# Power_Sheet.net
KiCad netlist of a schematic drawn in Altium Designer
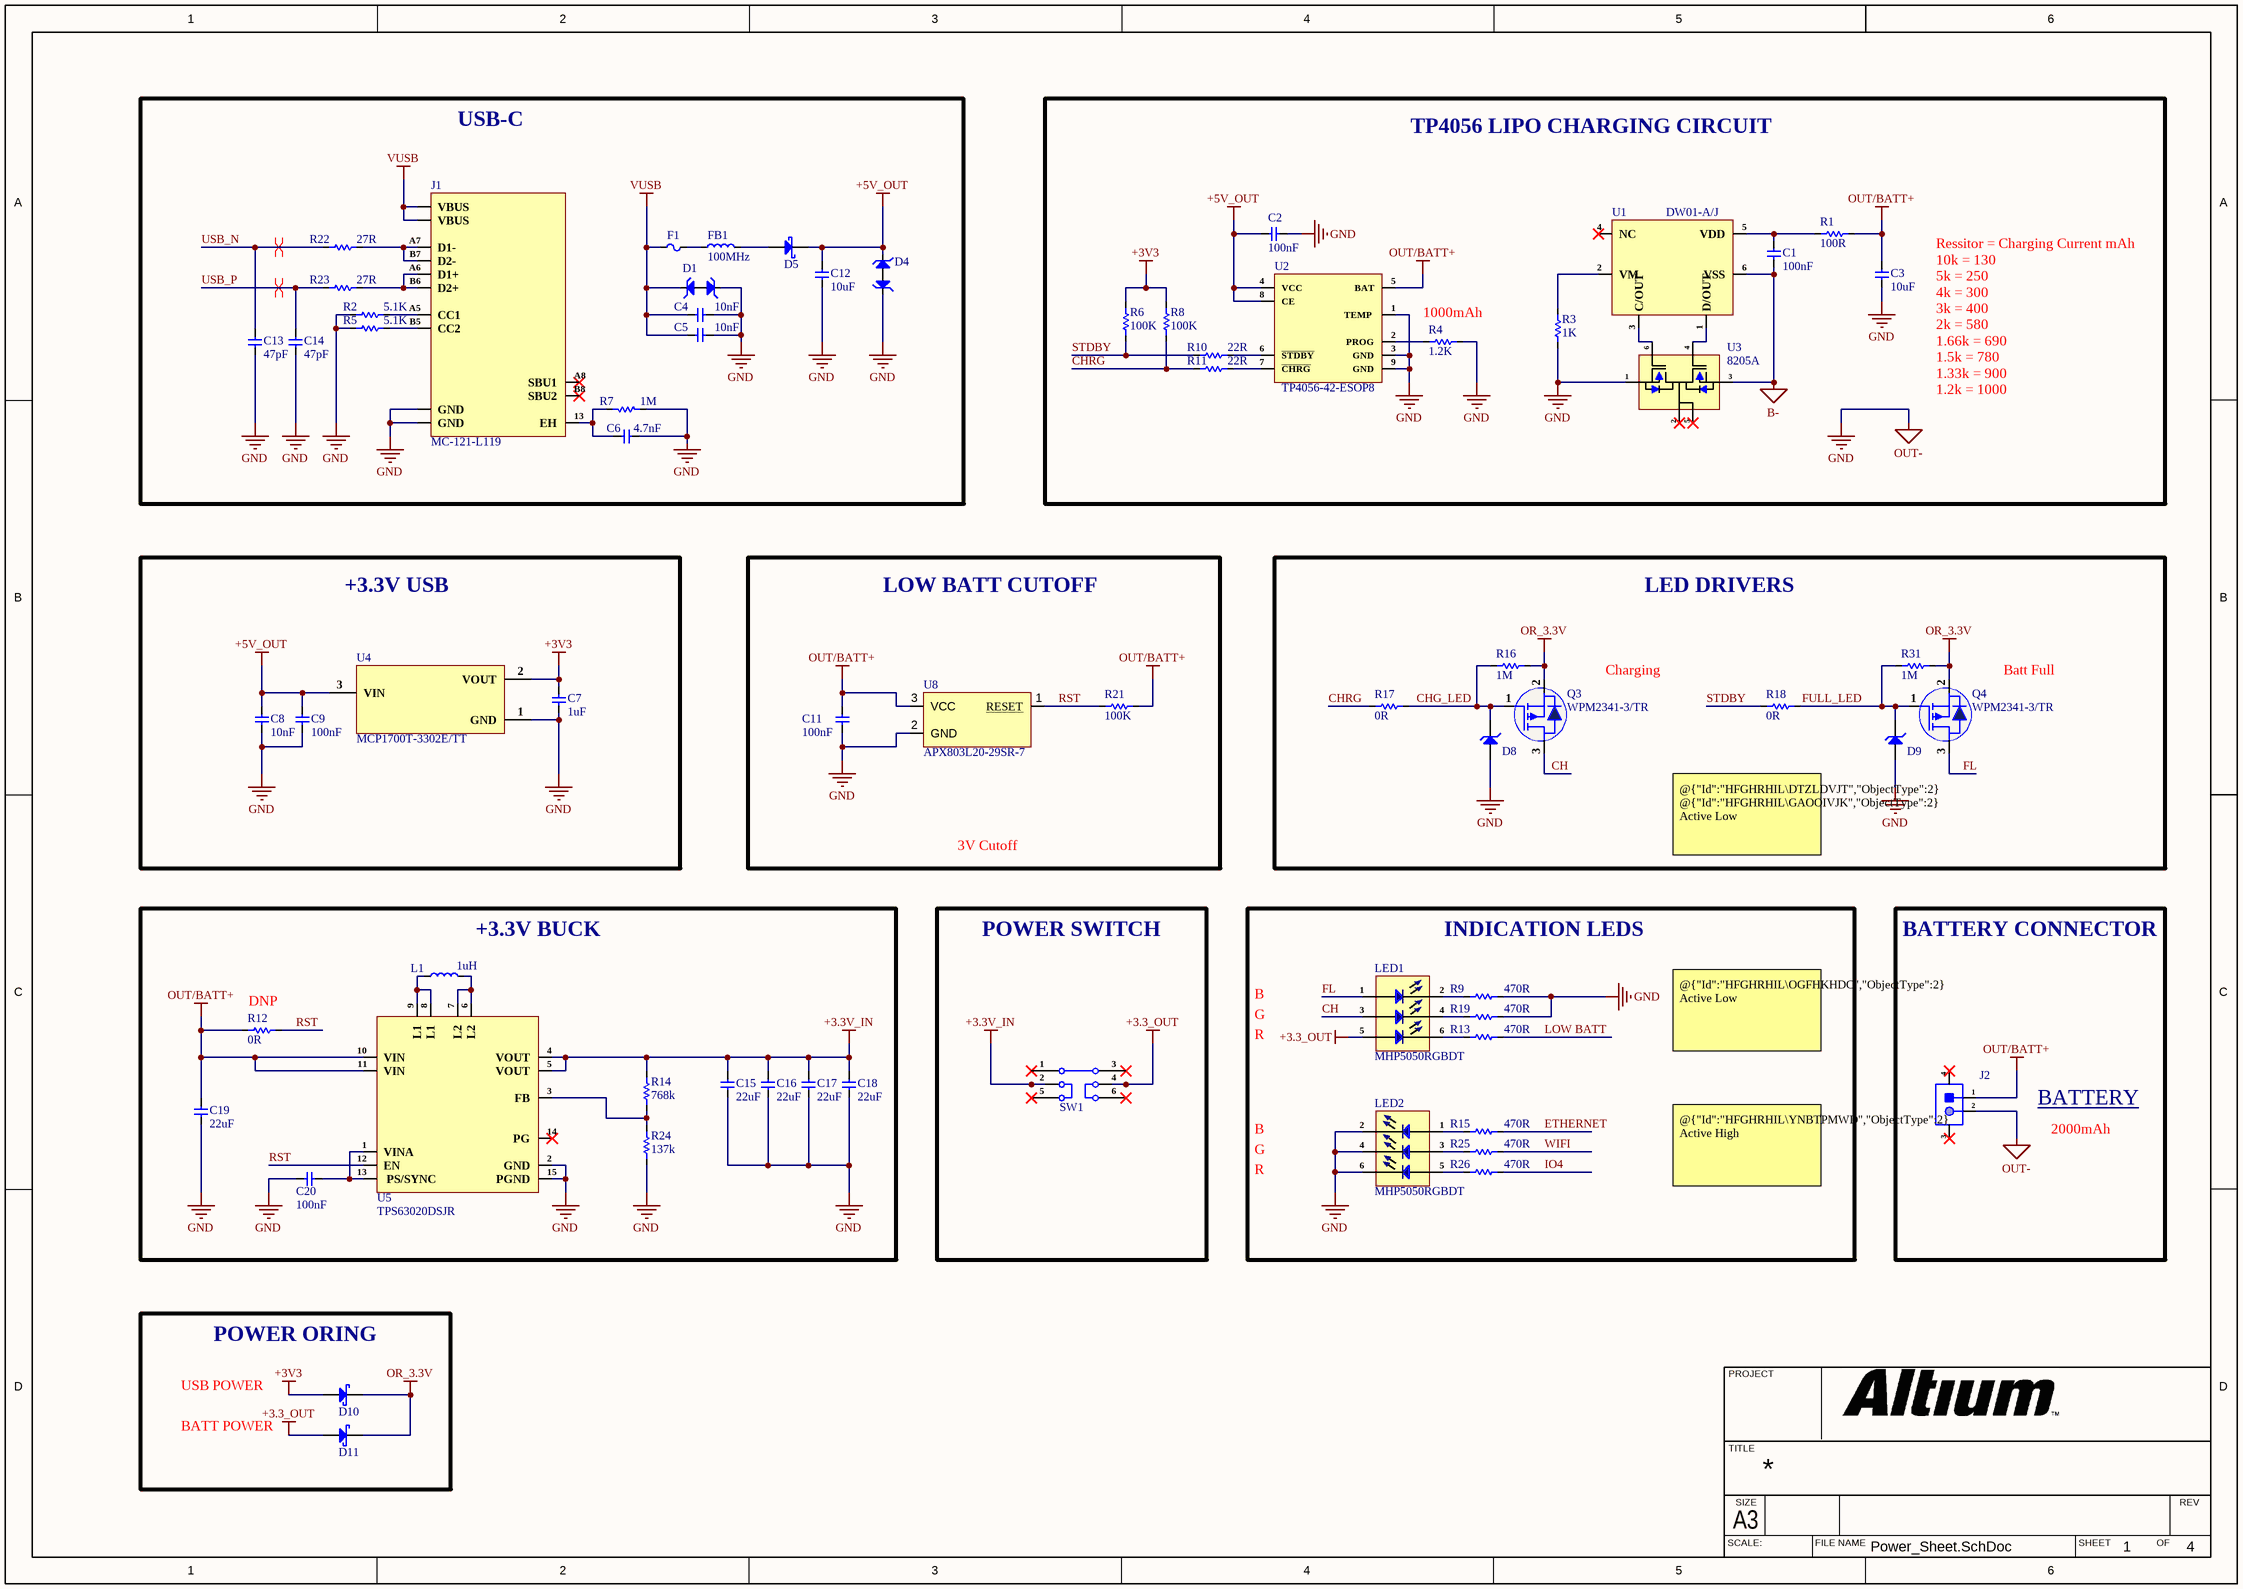
[diagram p0: Power_Sheet.SchDoc]

(export (version "E")
  (design (tool "Eeschema 10.0.6"))
  (components
    (comp (ref "C1")
      (value "100nF")
      (footprint "cap-0402")
      (description "CAP CER 0.1UF 50V X7R 0402")
      (fields
        (field (name "MANUFACTURER") "TDK")
        (field (name "MANUFACTURER PART NUMBER") "C1005X7R1H104KT000F")
      )
      (libsource (lib "eSpark Libraries") (part "C1005X7R1H104KT000F"))
    )
    (comp (ref "C2")
      (value "100nF")
      (footprint "cap-0402")
      (description "CAP CER 0.1UF 50V X7R 0402")
      (fields
        (field (name "MANUFACTURER") "TDK")
        (field (name "MANUFACTURER PART NUMBER") "C1005X7R1H104KT000F")
      )
      (libsource (lib "eSpark Libraries") (part "C1005X7R1H104KT000F"))
    )
    (comp (ref "C3")
      (value "10uF")
      (footprint "Cap-0402")
      (description "CAP CER 10UF 10V X5R 0402")
      (fields
        (field (name "MANUFACTURER") "Samsung")
        (field (name "MANUFACTURER PART NUMBER") "CL05A106MP5NUNC")
      )
      (libsource (lib "eSpark Libraries") (part "CL05A106MP5NUNC"))
    )
    (comp (ref "C4")
      (value "10nF")
      (footprint "Cap-0402")
      (description "CAP CER 10000PF 25V X7R 0402")
      (fields
        (field (name "MANUFACTURER") "Yageo")
        (field (name "MANUFACTURER PART NUMBER") "CC0402KRX7R8BB103")
      )
      (libsource (lib "eSpark Libraries") (part "CC0402KRX7R8BB103"))
    )
    (comp (ref "C5")
      (value "10nF")
      (footprint "Cap-0402")
      (description "CAP CER 10000PF 25V X7R 0402")
      (fields
        (field (name "MANUFACTURER") "Yageo")
        (field (name "MANUFACTURER PART NUMBER") "CC0402KRX7R8BB103")
      )
      (libsource (lib "eSpark Libraries") (part "CC0402KRX7R8BB103"))
    )
    (comp (ref "C6")
      (value "4.7nF")
      (footprint "Cap-0402")
      (description "CAP CER 4700PF 50V X7R 0402")
      (fields
        (field (name "MANUFACTURER") "Yageo")
        (field (name "MANUFACTURER PART NUMBER") "CC0402KRX7R9BB472")
      )
      (libsource (lib "eSpark Libraries") (part "CC0402KRX7R9BB472"))
    )
    (comp (ref "C7")
      (value "1uF")
      (footprint "Cap-0402")
      (description "CAP CER 1UF 10V X5R 0402")
      (fields
        (field (name "MANUFACTURER") "Yageo")
        (field (name "MANUFACTURER PART NUMBER") "CC0402KRX5R6BB105")
      )
      (libsource (lib "eSpark Libraries") (part "CC0402KRX5R6BB105"))
    )
    (comp (ref "C8")
      (value "10nF")
      (footprint "Cap-0402")
      (description "CAP CER 10000PF 25V X7R 0402")
      (fields
        (field (name "MANUFACTURER") "Yageo")
        (field (name "MANUFACTURER PART NUMBER") "CC0402KRX7R8BB103")
      )
      (libsource (lib "eSpark Libraries") (part "CC0402KRX7R8BB103"))
    )
    (comp (ref "C9")
      (value "100nF")
      (footprint "cap-0402")
      (description "CAP CER 0.1UF 50V X7R 0402")
      (fields
        (field (name "MANUFACTURER") "TDK")
        (field (name "MANUFACTURER PART NUMBER") "C1005X7R1H104KT000F")
      )
      (libsource (lib "eSpark Libraries") (part "C1005X7R1H104KT000F"))
    )
    (comp (ref "C11")
      (value "100nF")
      (footprint "cap-0402")
      (description "CAP CER 0.1UF 50V X7R 0402")
      (fields
        (field (name "MANUFACTURER") "TDK")
        (field (name "MANUFACTURER PART NUMBER") "C1005X7R1H104KT000F")
      )
      (libsource (lib "eSpark Libraries") (part "C1005X7R1H104KT000F"))
    )
    (comp (ref "C12")
      (value "10uF")
      (footprint "Cap-0603")
      (description "CAP CER 10UF 25V X5R 0603")
      (fields
        (field (name "MANUFACTURER") "Samsung")
        (field (name "MANUFACTURER PART NUMBER") "CL10A106MA8NRNC")
      )
      (libsource (lib "eSpark Libraries") (part "CL10A106MA8NRNC"))
    )
    (comp (ref "C13")
      (value "47pF")
      (footprint "Cap-0402")
      (description "CAP CER 47PF 50V C0G/NP0 0402")
      (fields
        (field (name "MANUFACTURER") "Murata")
        (field (name "MANUFACTURER PART NUMBER") "GCM1555C1H470FA16D")
      )
      (libsource (lib "eSpark Libraries") (part "GCM1555C1H470FA16D"))
    )
    (comp (ref "C14")
      (value "47pF")
      (footprint "Cap-0402")
      (description "CAP CER 47PF 50V C0G/NP0 0402")
      (fields
        (field (name "MANUFACTURER") "Murata")
        (field (name "MANUFACTURER PART NUMBER") "GCM1555C1H470FA16D")
      )
      (libsource (lib "eSpark Libraries") (part "GCM1555C1H470FA16D"))
    )
    (comp (ref "C15")
      (value "22uF")
      (footprint "Cap-0805")
      (description "CAP CER 22UF 35V X5R 0805")
      (fields
        (field (name "MANUFACTURER") "TDK Corporation")
        (field (name "MANUFACTURER PART NUMBER") "C2012X5R1V226MT000E")
      )
      (libsource (lib "eSpark Libraries") (part "C2012X5R1V226MT000E"))
    )
    (comp (ref "C16")
      (value "22uF")
      (footprint "Cap-0805")
      (description "CAP CER 22UF 35V X5R 0805")
      (fields
        (field (name "MANUFACTURER") "TDK Corporation")
        (field (name "MANUFACTURER PART NUMBER") "C2012X5R1V226MT000E")
      )
      (libsource (lib "eSpark Libraries") (part "C2012X5R1V226MT000E"))
    )
    (comp (ref "C17")
      (value "22uF")
      (footprint "Cap-0805")
      (description "CAP CER 22UF 35V X5R 0805")
      (fields
        (field (name "MANUFACTURER") "TDK Corporation")
        (field (name "MANUFACTURER PART NUMBER") "C2012X5R1V226MT000E")
      )
      (libsource (lib "eSpark Libraries") (part "C2012X5R1V226MT000E"))
    )
    (comp (ref "C18")
      (value "22uF")
      (footprint "Cap-0805")
      (description "CAP CER 22UF 35V X5R 0805")
      (fields
        (field (name "MANUFACTURER") "TDK Corporation")
        (field (name "MANUFACTURER PART NUMBER") "C2012X5R1V226MT000E")
      )
      (libsource (lib "eSpark Libraries") (part "C2012X5R1V226MT000E"))
    )
    (comp (ref "C19")
      (value "22uF")
      (footprint "Cap-0805")
      (description "CAP CER 22UF 35V X5R 0805")
      (fields
        (field (name "MANUFACTURER") "TDK Corporation")
        (field (name "MANUFACTURER PART NUMBER") "C2012X5R1V226MT000E")
      )
      (libsource (lib "eSpark Libraries") (part "C2012X5R1V226MT000E"))
    )
    (comp (ref "C20")
      (value "100nF")
      (footprint "cap-0402")
      (description "CAP CER 0.1UF 50V X7R 0402")
      (fields
        (field (name "MANUFACTURER") "TDK")
        (field (name "MANUFACTURER PART NUMBER") "C1005X7R1H104KT000F")
      )
      (libsource (lib "eSpark Libraries") (part "C1005X7R1H104KT000F"))
    )
    (comp (ref "D1")
      (value "PESD5V0H1BSFYL")
      (footprint "DSN0603-2")
      (description "TVS DIODE 5VWM 6.3VC DSN0603-2")
      (fields (field (name "MANUFACTURER") "Nexperia") (field (name "LCSC PART NUMBER") "C477989"))
      (libsource (lib "eSpark Libraries") (part "PESD5V0H1BSFYL"))
    )
    (comp (ref "D4")
      (value "PESD5V0H1BSFYL")
      (footprint "DSN0603-2")
      (description "TVS DIODE 5VWM 6.3VC DSN0603-2")
      (fields (field (name "MANUFACTURER") "Nexperia") (field (name "LCSC PART NUMBER") "C477989"))
      (libsource (lib "eSpark Libraries") (part "PESD5V0H1BSFYL"))
    )
    (comp (ref "D5")
      (value "PMEG3010ER,115")
      (footprint "SOD-123W")
      (description "DIODE SCHOTTKY 30V 1A SOD123W")
      (fields (field (name "MANUFACTURER") "Nexperia") (field (name "LCSC PART NUMBER") "C456106"))
      (libsource (lib "eSpark Libraries") (part "PMEG3010ER,115"))
    )
    (comp (ref "D8")
      (value "MM3Z3V3")
      (footprint "SOD-323")
      (description "±5% Single 3.1V~3.5V 300mW 3.3V SOD-323 Zener Diodes ROHS")
      (fields (field (name "MANUFACTURER") "JSMSEMI") (field (name "LCSC PART NUMBER") "C123917"))
      (libsource (lib "eSpark Libraries") (part "MM3Z3V3"))
    )
    (comp (ref "D9")
      (value "MM3Z3V3")
      (footprint "SOD-323")
      (description "±5% Single 3.1V~3.5V 300mW 3.3V SOD-323 Zener Diodes ROHS")
      (fields (field (name "MANUFACTURER") "JSMSEMI") (field (name "LCSC PART NUMBER") "C123917"))
      (libsource (lib "eSpark Libraries") (part "MM3Z3V3"))
    )
    (comp (ref "D10")
      (value "RB521S-30")
      (footprint "SOD-523")
      (description "30V 500mV@200mA 200mA SOD-523 Schottky Barrier Diodes (SBD) ROHS")
      (fields
        (field (name "MANUFACTURER") "Jiangsu Changjing Electronics")
        (field (name "LCSC PART NUMBER") "C8523")
      )
      (libsource (lib "eSpark Libraries") (part "RB521S-30"))
    )
    (comp (ref "D11")
      (value "RB521S-30")
      (footprint "SOD-523")
      (description "30V 500mV@200mA 200mA SOD-523 Schottky Barrier Diodes (SBD) ROHS")
      (fields
        (field (name "MANUFACTURER") "Jiangsu Changjing Electronics")
        (field (name "LCSC PART NUMBER") "C8523")
      )
      (libsource (lib "eSpark Libraries") (part "RB521S-30"))
    )
    (comp (ref "F1")
      (value "BSMD0805L-200")
      (footprint "Fuse-0805")
      (description "6V 2A 50A 1W -40℃~+85℃ 4A 4mΩ 5s 45mΩ 0805 Resettable Fuses ROHS")
      (fields (field (name "MANUFACTURER") "BHFUSE") (field (name "LCSC PART NUMBER") "C2757931"))
      (libsource (lib "eSpark Libraries") (part "BSMD0805L-200"))
    )
    (comp (ref "FB1")
      (value "100MHz")
      (footprint "IND-1206")
      (description "FERRITE BEAD 120 OHM 1206 1LN")
      (fields
        (field (name "MANUFACTURER") "Murata")
        (field (name "MANUFACTURER PART NUMBER") "BLM31PG121SN1L")
      )
      (libsource (lib "eSpark Libraries") (part "BLM31PG121SN1L"))
    )
    (comp (ref "J1")
      (value "MC-121-L119")
      (footprint "MC-121-L119")
      (description "5A USB 3.1 1 Surface Mount 16P Female -40℃~+85℃ Type-C SMD USB Connectors ROHS")
      (fields (field (name "MANUFACTURER") "Hanbo Electronic") (field (name "LCSC PART NUMBER") "C6332278"))
      (libsource (lib "eSpark Libraries") (part "MC-121-L119"))
    )
    (comp (ref "J2")
      (value "S2B-PH-SM4-TB(LF)(SN)")
      (footprint "S2B-PH-SM4-TB(LF)(SN)")
      (fields (field (name "MANUFACTURER") "JST") (field (name "LCSC PART NUMBER") "C295747"))
      (libsource (lib "eSpark Libraries") (part "S2B-PH-SM4-TB(LF)(SN)"))
    )
    (comp (ref "L1")
      (value "1uH")
      (footprint "IND-1008 (2520 Metric)")
      (description "FIXED IND 1UH 3.2A 0.042OHM SMD")
      (fields (field (name "LCSC PART NUMBER") "C882955") (field (name "MANUFACTURER") "Murata"))
      (libsource (lib "eSpark Libraries") (part "DFE252012P-1R0M=P2"))
    )
    (comp (ref "LED1")
      (value "MHP5050RGBDT")
      (footprint "MHP5050RGBDT")
      (description "20mA White Diffused -40℃~+85℃ RGB SMD5050 Light Emitting Diodes (LED) ROHS")
      (fields (field (name "MANUFACTURER") "MEIHUA") (field (name "LCSC PART NUMBER") "C409780"))
      (libsource (lib "") (part "MHP5050RGBDT_1"))
    )
    (comp (ref "LED2")
      (value "MHP5050RGBDT")
      (footprint "MHP5050RGBDT")
      (description "20mA White Diffused -40℃~+85℃ RGB SMD5050 Light Emitting Diodes (LED) ROHS")
      (fields (field (name "MANUFACTURER") "MEIHUA") (field (name "LCSC PART NUMBER") "C409780"))
      (libsource (lib "eSpark Libraries") (part "MHP5050RGBDT"))
    )
    (comp (ref "Q3")
      (value "WPM2341-3/TR")
      (footprint "Sot-23")
      (description "20V 3.5A 750mW 61mΩ@4.5V,3.3A 1V@250uA 1PCSPChannel SOT-23 MOSFETs ROHS")
      (fields (field (name "MANUFACTURER") "WILLSEMI") (field (name "LCSC PART NUMBER") "C167138"))
      (libsource (lib "eSpark Libraries") (part "WPM2341-3/TR"))
    )
    (comp (ref "Q4")
      (value "WPM2341-3/TR")
      (footprint "Sot-23")
      (description "20V 3.5A 750mW 61mΩ@4.5V,3.3A 1V@250uA 1PCSPChannel SOT-23 MOSFETs ROHS")
      (fields (field (name "MANUFACTURER") "WILLSEMI") (field (name "LCSC PART NUMBER") "C167138"))
      (libsource (lib "eSpark Libraries") (part "WPM2341-3/TR"))
    )
    (comp (ref "R1")
      (value "100R")
      (footprint "RES-0805")
      (description "RES SMD 100 OHM 1% 1/8W 0805")
      (fields
        (field (name "MANUFACTURER") "Yageo")
        (field (name "MANUFACTURER PART NUMBER") "AC0805FR-07100RL")
      )
      (libsource (lib "eSpark Libraries") (part "AC0805FR-07100RL"))
    )
    (comp (ref "R2")
      (value "5.1K")
      (footprint "Res-0402")
      (description "RES 5.1K OHM 1% 1/16W 0402")
      (fields
        (field (name "MANUFACTURER") "Yageo")
        (field (name "MANUFACTURER PART NUMBER") "RC0402FR-075K1L")
      )
      (libsource (lib "eSpark Libraries") (part "RC0402FR-075K1L"))
    )
    (comp (ref "R3")
      (value "1K")
      (footprint "Res-0402")
      (description "RES SMD 1K OHM 1% 1/5W 0402")
      (fields
        (field (name "MANUFACTURER") "Vishay Dale")
        (field (name "MANUFACTURER PART NUMBER") "CRCW04021K00FKEDHP")
      )
      (libsource (lib "eSpark Libraries") (part "CRCW04021K00FKEDHP"))
    )
    (comp (ref "R4")
      (value "1.2K")
      (footprint "Res-0402")
      (description "RES 1.2K OHM 1% 1/16W 0402")
      (fields
        (field (name "MANUFACTURER") "Yageo")
        (field (name "MANUFACTURER PART NUMBER") "RC0402FR-071K2L")
      )
      (libsource (lib "eSpark Libraries") (part "RC0402FR-071K2L"))
    )
    (comp (ref "R5")
      (value "5.1K")
      (footprint "Res-0402")
      (description "RES 5.1K OHM 1% 1/16W 0402")
      (fields
        (field (name "MANUFACTURER") "Yageo")
        (field (name "MANUFACTURER PART NUMBER") "RC0402FR-075K1L")
      )
      (libsource (lib "eSpark Libraries") (part "RC0402FR-075K1L"))
    )
    (comp (ref "R6")
      (value "100K")
      (footprint "Res-0402")
      (description "RES 100K OHM 1% 1/16W 0402")
      (fields
        (field (name "MANUFACTURER") "Yageo")
        (field (name "MANUFACTURER PART NUMBER") "RC0402FR-07100KL")
      )
      (libsource (lib "eSpark Libraries") (part "RC0402FR-07100KL"))
    )
    (comp (ref "R7")
      (value "1M")
      (footprint "Res-0402")
      (description "RES SMD 1M OHM 5% 1/16W 0402")
      (fields
        (field (name "MANUFACTURER") "Yageo")
        (field (name "MANUFACTURER PART NUMBER") "AF0402JR-071ML")
      )
      (libsource (lib "eSpark Libraries") (part "AF0402JR-071ML"))
    )
    (comp (ref "R8")
      (value "100K")
      (footprint "Res-0402")
      (description "RES 100K OHM 1% 1/16W 0402")
      (fields
        (field (name "MANUFACTURER") "Yageo")
        (field (name "MANUFACTURER PART NUMBER") "RC0402FR-07100KL")
      )
      (libsource (lib "eSpark Libraries") (part "RC0402FR-07100KL"))
    )
    (comp (ref "R9")
      (value "470R")
      (footprint "Res-0402")
      (description "RES 470 OHM 1% 1/16W 0402")
      (fields
        (field (name "MANUFACTURER") "Yageo")
        (field (name "MANUFACTURER PART NUMBER") "RC0402FR-07470RL")
      )
      (libsource (lib "eSpark Libraries") (part "RC0402FR-07470RL"))
    )
    (comp (ref "R10")
      (value "22R")
      (footprint "Res-0402")
      (description "RES 22 OHM 1% 1/16W 0402")
      (fields
        (field (name "MANUFACTURER") "Yageo")
        (field (name "MANUFACTURER PART NUMBER") "RC0402FR-0722RL")
      )
      (libsource (lib "eSpark Libraries") (part "RC0402FR-0722RL"))
    )
    (comp (ref "R11")
      (value "22R")
      (footprint "Res-0402")
      (description "RES 22 OHM 1% 1/16W 0402")
      (fields
        (field (name "MANUFACTURER") "Yageo")
        (field (name "MANUFACTURER PART NUMBER") "RC0402FR-0722RL")
      )
      (libsource (lib "eSpark Libraries") (part "RC0402FR-0722RL"))
    )
    (comp (ref "R12")
      (value "0R")
      (footprint "Res-0402")
      (description "RES 0 OHM JUMPER 1/16W 0402")
      (fields
        (field (name "MANUFACTURER") "Yageo")
        (field (name "MANUFACTURER PART NUMBER") "RC0402FR-070RL")
      )
      (libsource (lib "eSpark Libraries") (part "RC0402FR-070RL"))
    )
    (comp (ref "R13")
      (value "470R")
      (footprint "Res-0402")
      (description "RES 470 OHM 1% 1/16W 0402")
      (fields
        (field (name "MANUFACTURER") "Yageo")
        (field (name "MANUFACTURER PART NUMBER") "RC0402FR-07470RL")
      )
      (libsource (lib "eSpark Libraries") (part "RC0402FR-07470RL"))
    )
    (comp (ref "R14")
      (value "768k")
      (footprint "Res-0402")
      (description "62.5mW Thick Film Resistor 50V ±100ppm/℃ ±1% 768kΩ 0402 Chip Resistor - Surface Mount ROHS")
      (fields
        (field (name "MANUFACTURER") "YAGEO")
        (field (name "MANUFACTURER PART NUMBER") "AC0402FR-07768KL")
      )
      (libsource (lib "eSpark Libraries") (part "AC0402FR-07768KL"))
    )
    (comp (ref "R15")
      (value "470R")
      (footprint "Res-0402")
      (description "RES 470 OHM 1% 1/16W 0402")
      (fields
        (field (name "MANUFACTURER") "Yageo")
        (field (name "MANUFACTURER PART NUMBER") "RC0402FR-07470RL")
      )
      (libsource (lib "eSpark Libraries") (part "RC0402FR-07470RL"))
    )
    (comp (ref "R16")
      (value "1M")
      (footprint "Res-0402")
      (description "RES 1M OHM 1% 1/16W 0402")
      (fields
        (field (name "MANUFACTURER") "Yageo")
        (field (name "MANUFACTURER PART NUMBER") "RC0402FR-071ML")
      )
      (libsource (lib "eSpark Libraries") (part "RC0402FR-071ML"))
    )
    (comp (ref "R17")
      (value "0R")
      (footprint "Res-0402")
      (description "RES 0 OHM JUMPER 1/16W 0402")
      (fields
        (field (name "MANUFACTURER") "Yageo")
        (field (name "MANUFACTURER PART NUMBER") "RC0402FR-070RL")
      )
      (libsource (lib "eSpark Libraries") (part "RC0402FR-070RL"))
    )
    (comp (ref "R18")
      (value "0R")
      (footprint "Res-0402")
      (description "RES 0 OHM JUMPER 1/16W 0402")
      (fields
        (field (name "MANUFACTURER") "Yageo")
        (field (name "MANUFACTURER PART NUMBER") "RC0402FR-070RL")
      )
      (libsource (lib "eSpark Libraries") (part "RC0402FR-070RL"))
    )
    (comp (ref "R19")
      (value "470R")
      (footprint "Res-0402")
      (description "RES 470 OHM 1% 1/16W 0402")
      (fields
        (field (name "MANUFACTURER") "Yageo")
        (field (name "MANUFACTURER PART NUMBER") "RC0402FR-07470RL")
      )
      (libsource (lib "eSpark Libraries") (part "RC0402FR-07470RL"))
    )
    (comp (ref "R21")
      (value "100K")
      (footprint "Res-0402")
      (description "RES 100K OHM 1% 1/16W 0402")
      (fields
        (field (name "MANUFACTURER") "Yageo")
        (field (name "MANUFACTURER PART NUMBER") "RC0402FR-07100KL")
      )
      (libsource (lib "eSpark Libraries") (part "RC0402FR-07100KL"))
    )
    (comp (ref "R22")
      (value "27R")
      (footprint "Res-0402")
      (description "62.5mW Thick Film Resistors 50V ±100ppm/℃ ±1% 27Ω 0402 Chip Resistor - Surface Mount ROHS")
      (fields
        (field (name "MANUFACTURER") "YAGEO")
        (field (name "MANUFACTURER PART NUMBER") "RC0402FR-0727RL")
      )
      (libsource (lib "eSpark Libraries") (part "RC0402FR-0727RL"))
    )
    (comp (ref "R23")
      (value "27R")
      (footprint "Res-0402")
      (description "62.5mW Thick Film Resistors 50V ±100ppm/℃ ±1% 27Ω 0402 Chip Resistor - Surface Mount ROHS")
      (fields
        (field (name "MANUFACTURER") "YAGEO")
        (field (name "MANUFACTURER PART NUMBER") "RC0402FR-0727RL")
      )
      (libsource (lib "eSpark Libraries") (part "RC0402FR-0727RL"))
    )
    (comp (ref "R24")
      (value "137k")
      (footprint "Res-0402")
      (description "62.5mW Thick Film Resistor 50V ±100ppm/℃ ±1% 137kΩ 0402 Chip Resistor - Surface Mount ROHS")
      (fields
        (field (name "MANUFACTURER") "FOJAN")
        (field (name "MANUFACTURER PART NUMBER") "FRC0402F1373TS")
      )
      (libsource (lib "eSpark Libraries") (part "FRC0402F1373TS"))
    )
    (comp (ref "R25")
      (value "470R")
      (footprint "Res-0402")
      (description "RES 470 OHM 1% 1/16W 0402")
      (fields
        (field (name "MANUFACTURER") "Yageo")
        (field (name "MANUFACTURER PART NUMBER") "RC0402FR-07470RL")
      )
      (libsource (lib "eSpark Libraries") (part "RC0402FR-07470RL"))
    )
    (comp (ref "R26")
      (value "470R")
      (footprint "Res-0402")
      (description "RES 470 OHM 1% 1/16W 0402")
      (fields
        (field (name "MANUFACTURER") "Yageo")
        (field (name "MANUFACTURER PART NUMBER") "RC0402FR-07470RL")
      )
      (libsource (lib "eSpark Libraries") (part "RC0402FR-07470RL"))
    )
    (comp (ref "R31")
      (value "1M")
      (footprint "Res-0402")
      (description "RES 1M OHM 1% 1/16W 0402")
      (fields
        (field (name "MANUFACTURER") "Yageo")
        (field (name "MANUFACTURER PART NUMBER") "RC0402FR-071ML")
      )
      (libsource (lib "eSpark Libraries") (part "RC0402FR-071ML"))
    )
    (comp (ref "SW1")
      (value "TK-6580A8-1")
      (footprint "TK-6580A8-1")
      (description "Latching Right Angle DPDT 2.5N Through Hole Pushbutton Switches ROHS")
      (fields (field (name "MANUFACTURER") "Yuandi") (field (name "LCSC PART NUMBER") "C528772"))
      (libsource (lib "eSpark Libraries") (part "TK-6580A8-1"))
    )
    (comp (ref "U1")
      (value "DW01-A/J")
      (footprint "SOT-23-6")
      (description "SOT-23-6 Battery Management ROHS")
      (fields
        (field (name "MANUFACTURER") "Shenzhen Fuman Elec")
        (field (name "LCSC PART NUMBER") "C2909013")
      )
      (libsource (lib "eSpark Libraries") (part "DW01-A/J"))
    )
    (comp (ref "U2")
      (value "TP4056-42-ESOP8")
      (footprint "ESOP-8")
      (description "ESOP-8 Battery Management ICs ROHS")
      (fields (field (name "MANUFACTURER") "TOPPOWER") (field (name "LCSC PART NUMBER") "C16581"))
      (libsource (lib "eSpark Libraries") (part "TP4056-42-ESOP8"))
    )
    (comp (ref "U3")
      (value "8205A")
      (footprint "SOT-23-6")
      (description "20V 5A 36mΩ@2.5V,3A 830mW 1.2V@250uA 2 N-Channel SOT-23-6 MOSFETs ROHS")
      (fields (field (name "MANUFACTURER") "UMW") (field (name "LCSC PART NUMBER") "C351449"))
      (libsource (lib "eSpark Libraries") (part "8205A"))
    )
    (comp (ref "U4")
      (value "MCP1700T-3302E/TT")
      (footprint "SOT-23")
      (description "IC REG LDO 3.3V 0.25A SOT23-3")
      (fields (field (name "MANUFACTURER") "Microchip"))
      (libsource (lib "eSpark Libraries") (part "MCP1700T-3302E/TT"))
    )
    (comp (ref "U5")
      (value "TPS63020DSJR")
      (footprint "14-VSON (4x3)")
      (description "IC REG BUCK-BST ADJ 3.5A 14VSON")
      (fields (field (name "MANUFACTURER") "Texas Instruments") (field (name "LCSC PART NUMBER") "C15483"))
      (libsource (lib "eSpark Libraries") (part "TPS63020DSJR"))
    )
    (comp (ref "U8")
      (value "APX803L20-29SR-7")
      (footprint "SOT-23")
      (description "20ms Active Low 900mV~5.5V 1 SOT-23R Supervisor and Reset ICs ROHS")
      (fields (field (name "MANUFACTURER") "DIODES") (field (name "LCSC PART NUMBER") "C5589080"))
      (libsource (lib "eSpark Libraries") (part "APX803L20-29SR-7"))
    )
  )
  (nets
    (net (code "1") (name "+3.3V_IN") (class "Default")
      (node (ref "C15") (pin "2") (pinfunction "2_2") (pintype "passive"))
      (node (ref "C16") (pin "2") (pinfunction "2_2") (pintype "passive"))
      (node (ref "C17") (pin "2") (pinfunction "2_2") (pintype "passive"))
      (node (ref "C18") (pin "2") (pinfunction "2_2") (pintype "passive"))
      (node (ref "R14") (pin "2") (pinfunction "2_2") (pintype "passive"))
      (node (ref "SW1") (pin "2") (pinfunction "2_2") (pintype "passive"))
      (node (ref "U5") (pin "4") (pinfunction "VOUT_4") (pintype "passive"))
      (node (ref "U5") (pin "5") (pinfunction "VOUT_5") (pintype "passive"))
    )
    (net (code "2") (name "+3.3_OUT") (class "Default")
      (node (ref "D11") (pin "1") (pinfunction "A_1") (pintype "passive"))
      (node (ref "LED1") (pin "5") (pinfunction "5_5") (pintype "passive"))
      (node (ref "SW1") (pin "4") (pinfunction "4_4") (pintype "passive"))
    )
    (net (code "3") (name "+3V3") (class "Default")
      (node (ref "C7") (pin "2") (pinfunction "2_2") (pintype "passive"))
      (node (ref "D10") (pin "1") (pinfunction "A_1") (pintype "passive"))
      (node (ref "R6") (pin "2") (pinfunction "2_2") (pintype "passive"))
      (node (ref "R8") (pin "2") (pinfunction "2_2") (pintype "passive"))
      (node (ref "U4") (pin "2") (pinfunction "VOUT_2") (pintype "passive"))
    )
    (net (code "4") (name "+5V_OUT") (class "Default")
      (node (ref "C12") (pin "2") (pinfunction "2_2") (pintype "passive"))
      (node (ref "C2") (pin "1") (pinfunction "1_1") (pintype "passive"))
      (node (ref "C8") (pin "1") (pinfunction "1_1") (pintype "passive"))
      (node (ref "C9") (pin "1") (pinfunction "1_1") (pintype "passive"))
      (node (ref "D4") (pin "2") (pinfunction "2_2") (pintype "passive"))
      (node (ref "D5") (pin "2") (pinfunction "K_2") (pintype "passive"))
      (node (ref "U2") (pin "4") (pinfunction "VCC_4") (pintype "passive"))
      (node (ref "U2") (pin "8") (pinfunction "CE_8") (pintype "passive"))
      (node (ref "U4") (pin "3") (pinfunction "VIN_3") (pintype "passive"))
    )
    (net (code "5") (name "/CH") (class "Default")
      (node (ref "LED1") (pin "3") (pinfunction "3_3") (pintype "passive"))
      (node (ref "Q3") (pin "3") (pinfunction "D_3") (pintype "passive"))
    )
    (net (code "6") (name "/CHG_LED") (class "Default")
      (node (ref "D8") (pin "1") (pinfunction "K_1") (pintype "passive"))
      (node (ref "Q3") (pin "1") (pinfunction "G_1") (pintype "passive"))
      (node (ref "R16") (pin "1") (pinfunction "1_1") (pintype "passive"))
      (node (ref "R17") (pin "2") (pinfunction "2_2") (pintype "passive"))
    )
    (net (code "7") (name "/CHRG") (class "Default")
      (node (ref "R11") (pin "1") (pinfunction "1_1") (pintype "passive"))
      (node (ref "R17") (pin "1") (pinfunction "1_1") (pintype "passive"))
      (node (ref "R8") (pin "1") (pinfunction "1_1") (pintype "passive"))
    )
    (net (code "8") (name "/ETHERNET") (class "Default")
      (node (ref "R15") (pin "1") (pinfunction "1_1") (pintype "passive"))
    )
    (net (code "9") (name "/FL") (class "Default")
      (node (ref "LED1") (pin "1") (pinfunction "1_1") (pintype "passive"))
      (node (ref "Q4") (pin "3") (pinfunction "D_3") (pintype "passive"))
    )
    (net (code "10") (name "/FULL_LED") (class "Default")
      (node (ref "D9") (pin "1") (pinfunction "K_1") (pintype "passive"))
      (node (ref "Q4") (pin "1") (pinfunction "G_1") (pintype "passive"))
      (node (ref "R18") (pin "2") (pinfunction "2_2") (pintype "passive"))
      (node (ref "R31") (pin "1") (pinfunction "1_1") (pintype "passive"))
    )
    (net (code "11") (name "/IO4") (class "Default")
      (node (ref "R26") (pin "1") (pinfunction "1_1") (pintype "passive"))
    )
    (net (code "12") (name "/LOW BATT") (class "Default")
      (node (ref "R13") (pin "1") (pinfunction "1_1") (pintype "passive"))
    )
    (net (code "13") (name "/RST") (class "Default")
      (node (ref "R12") (pin "2") (pinfunction "2_2") (pintype "passive"))
      (node (ref "R21") (pin "2") (pinfunction "2_2") (pintype "passive"))
      (node (ref "U5") (pin "12") (pinfunction "EN_12") (pintype "passive"))
      (node (ref "U8") (pin "1") (pinfunction "RESET_1") (pintype "passive"))
    )
    (net (code "14") (name "/STDBY") (class "Default")
      (node (ref "R10") (pin "1") (pinfunction "1_1") (pintype "passive"))
      (node (ref "R18") (pin "1") (pinfunction "1_1") (pintype "passive"))
      (node (ref "R6") (pin "1") (pinfunction "1_1") (pintype "passive"))
    )
    (net (code "15") (name "/USB_N") (class "Default")
      (node (ref "C13") (pin "2") (pinfunction "2_2") (pintype "passive"))
      (node (ref "R22") (pin "1") (pinfunction "1_1") (pintype "passive"))
    )
    (net (code "16") (name "/USB_P") (class "Default")
      (node (ref "C14") (pin "2") (pinfunction "2_2") (pintype "passive"))
      (node (ref "R23") (pin "1") (pinfunction "1_1") (pintype "passive"))
    )
    (net (code "17") (name "/WIFI") (class "Default")
      (node (ref "R25") (pin "1") (pinfunction "1_1") (pintype "passive"))
    )
    (net (code "18") (name "B-") (class "Default")
      (node (ref "C1") (pin "2") (pinfunction "2_2") (pintype "passive"))
      (node (ref "U1") (pin "6") (pinfunction "VSS_6") (pintype "passive"))
      (node (ref "U3") (pin "3") (pinfunction "S2_3") (pintype "passive"))
    )
    (net (code "19") (name "GND") (class "Default")
      (node (ref "C11") (pin "2") (pinfunction "2_2") (pintype "passive"))
      (node (ref "C12") (pin "1") (pinfunction "1_1") (pintype "passive"))
      (node (ref "C13") (pin "1") (pinfunction "1_1") (pintype "passive"))
      (node (ref "C14") (pin "1") (pinfunction "1_1") (pintype "passive"))
      (node (ref "C15") (pin "1") (pinfunction "1_1") (pintype "passive"))
      (node (ref "C16") (pin "1") (pinfunction "1_1") (pintype "passive"))
      (node (ref "C17") (pin "1") (pinfunction "1_1") (pintype "passive"))
      (node (ref "C18") (pin "1") (pinfunction "1_1") (pintype "passive"))
      (node (ref "C19") (pin "1") (pinfunction "1_1") (pintype "passive"))
      (node (ref "C2") (pin "2") (pinfunction "2_2") (pintype "passive"))
      (node (ref "C20") (pin "2") (pinfunction "2_2") (pintype "passive"))
      (node (ref "C3") (pin "1") (pinfunction "1_1") (pintype "passive"))
      (node (ref "C4") (pin "2") (pinfunction "2_2") (pintype "passive"))
      (node (ref "C5") (pin "2") (pinfunction "2_2") (pintype "passive"))
      (node (ref "C6") (pin "1") (pinfunction "1_1") (pintype "passive"))
      (node (ref "C7") (pin "1") (pinfunction "1_1") (pintype "passive"))
      (node (ref "C8") (pin "2") (pinfunction "2_2") (pintype "passive"))
      (node (ref "C9") (pin "2") (pinfunction "2_2") (pintype "passive"))
      (node (ref "D1") (pin "2") (pinfunction "2_2") (pintype "passive"))
      (node (ref "D4") (pin "1") (pinfunction "1_1") (pintype "passive"))
      (node (ref "D8") (pin "2") (pinfunction "A_2") (pintype "passive"))
      (node (ref "D9") (pin "2") (pinfunction "A_2") (pintype "passive"))
      (node (ref "J1") (pin "A1B12") (pinfunction "GND_A1B12") (pintype "passive"))
      (node (ref "J1") (pin "B1A12") (pinfunction "GND_B1A12") (pintype "passive"))
      (node (ref "J2") (pin "2") (pinfunction "2_2") (pintype "passive"))
      (node (ref "LED2") (pin "2") (pinfunction "2_2") (pintype "passive"))
      (node (ref "LED2") (pin "4") (pinfunction "4_4") (pintype "passive"))
      (node (ref "LED2") (pin "6") (pinfunction "6_6") (pintype "passive"))
      (node (ref "R19") (pin "1") (pinfunction "1_1") (pintype "passive"))
      (node (ref "R2") (pin "1") (pinfunction "1_1") (pintype "passive"))
      (node (ref "R24") (pin "1") (pinfunction "1_1") (pintype "passive"))
      (node (ref "R3") (pin "1") (pinfunction "1_1") (pintype "passive"))
      (node (ref "R4") (pin "2") (pinfunction "2_2") (pintype "passive"))
      (node (ref "R5") (pin "1") (pinfunction "1_1") (pintype "passive"))
      (node (ref "R7") (pin "1") (pinfunction "1_1") (pintype "passive"))
      (node (ref "R9") (pin "1") (pinfunction "1_1") (pintype "passive"))
      (node (ref "U2") (pin "1") (pinfunction "TEMP_1") (pintype "passive"))
      (node (ref "U2") (pin "3") (pinfunction "GND_3") (pintype "passive"))
      (node (ref "U2") (pin "9") (pinfunction "GND_9") (pintype "passive"))
      (node (ref "U3") (pin "1") (pinfunction "S1_1") (pintype "passive"))
      (node (ref "U4") (pin "1") (pinfunction "GND_1") (pintype "passive"))
      (node (ref "U5") (pin "15") (pinfunction "PGND_15") (pintype "passive"))
      (node (ref "U5") (pin "2") (pinfunction "GND_2") (pintype "passive"))
      (node (ref "U8") (pin "2") (pinfunction "GND_2") (pintype "passive"))
    )
    (net (code "20") (name "Net-(D5-A)") (class "Default")
      (node (ref "D5") (pin "1") (pinfunction "A_1") (pintype "passive"))
      (node (ref "FB1") (pin "2") (pinfunction "2_2") (pintype "passive"))
    )
    (net (code "21") (name "Net-(F1-Pad2)") (class "Default")
      (node (ref "F1") (pin "2") (pinfunction "2_2") (pintype "passive"))
      (node (ref "FB1") (pin "1") (pinfunction "1_1") (pintype "passive"))
    )
    (net (code "22") (name "Net-(J1-CC1)") (class "Default")
      (node (ref "J1") (pin "A5") (pinfunction "CC1_A5") (pintype "passive"))
      (node (ref "R2") (pin "2") (pinfunction "2_2") (pintype "passive"))
    )
    (net (code "23") (name "Net-(J1-CC2)") (class "Default")
      (node (ref "J1") (pin "B5") (pinfunction "CC2_B5") (pintype "passive"))
      (node (ref "R5") (pin "2") (pinfunction "2_2") (pintype "passive"))
    )
    (net (code "24") (name "Net-(J1-D1+)") (class "Default")
      (node (ref "J1") (pin "A6") (pinfunction "D1+_A6") (pintype "passive"))
      (node (ref "J1") (pin "B6") (pinfunction "D2+_B6") (pintype "passive"))
      (node (ref "R23") (pin "2") (pinfunction "2_2") (pintype "passive"))
    )
    (net (code "25") (name "Net-(J1-D1-)") (class "Default")
      (node (ref "J1") (pin "A7") (pinfunction "D1-_A7") (pintype "passive"))
      (node (ref "J1") (pin "B7") (pinfunction "D2-_B7") (pintype "passive"))
      (node (ref "R22") (pin "2") (pinfunction "2_2") (pintype "passive"))
    )
    (net (code "26") (name "Net-(J1-EH)") (class "Default")
      (node (ref "C6") (pin "2") (pinfunction "2_2") (pintype "passive"))
      (node (ref "J1") (pin "13") (pinfunction "EH_13") (pintype "passive"))
      (node (ref "R7") (pin "2") (pinfunction "2_2") (pintype "passive"))
    )
    (net (code "27") (name "Net-(L1-Pad1)") (class "Default")
      (node (ref "L1") (pin "1") (pinfunction "1_1") (pintype "passive"))
      (node (ref "U5") (pin "8") (pinfunction "L1_8") (pintype "passive"))
      (node (ref "U5") (pin "9") (pinfunction "L1_9") (pintype "passive"))
    )
    (net (code "28") (name "Net-(L1-Pad2)") (class "Default")
      (node (ref "L1") (pin "2") (pinfunction "2_2") (pintype "passive"))
      (node (ref "U5") (pin "6") (pinfunction "L2_6") (pintype "passive"))
      (node (ref "U5") (pin "7") (pinfunction "L2_7") (pintype "passive"))
    )
    (net (code "29") (name "Net-(LED1-Pad2)") (class "Default")
      (node (ref "LED1") (pin "2") (pinfunction "2_2") (pintype "passive"))
      (node (ref "R9") (pin "2") (pinfunction "2_2") (pintype "passive"))
    )
    (net (code "30") (name "Net-(LED1-Pad4)") (class "Default")
      (node (ref "LED1") (pin "4") (pinfunction "4_4") (pintype "passive"))
      (node (ref "R19") (pin "2") (pinfunction "2_2") (pintype "passive"))
    )
    (net (code "31") (name "Net-(LED1-Pad6)") (class "Default")
      (node (ref "LED1") (pin "6") (pinfunction "6_6") (pintype "passive"))
      (node (ref "R13") (pin "2") (pinfunction "2_2") (pintype "passive"))
    )
    (net (code "32") (name "Net-(LED2-Pad1)") (class "Default")
      (node (ref "LED2") (pin "1") (pinfunction "1_1") (pintype "passive"))
      (node (ref "R15") (pin "2") (pinfunction "2_2") (pintype "passive"))
    )
    (net (code "33") (name "Net-(LED2-Pad3)") (class "Default")
      (node (ref "LED2") (pin "3") (pinfunction "3_3") (pintype "passive"))
      (node (ref "R25") (pin "2") (pinfunction "2_2") (pintype "passive"))
    )
    (net (code "34") (name "Net-(LED2-Pad5)") (class "Default")
      (node (ref "LED2") (pin "5") (pinfunction "5_5") (pintype "passive"))
      (node (ref "R26") (pin "2") (pinfunction "2_2") (pintype "passive"))
    )
    (net (code "35") (name "Net-(U1-C{slash}OUT)") (class "Default")
      (node (ref "U1") (pin "3") (pinfunction "C/OUT_3") (pintype "passive"))
      (node (ref "U3") (pin "6") (pinfunction "G1_6") (pintype "passive"))
    )
    (net (code "36") (name "Net-(U1-D{slash}OUT)") (class "Default")
      (node (ref "U1") (pin "1") (pinfunction "D/OUT_1") (pintype "passive"))
      (node (ref "U3") (pin "4") (pinfunction "G2_4") (pintype "passive"))
    )
    (net (code "37") (name "Net-(U1-VDD)") (class "Default")
      (node (ref "C1") (pin "1") (pinfunction "1_1") (pintype "passive"))
      (node (ref "R1") (pin "1") (pinfunction "1_1") (pintype "passive"))
      (node (ref "U1") (pin "5") (pinfunction "VDD_5") (pintype "passive"))
    )
    (net (code "38") (name "Net-(U1-VM)") (class "Default")
      (node (ref "R3") (pin "2") (pinfunction "2_2") (pintype "passive"))
      (node (ref "U1") (pin "2") (pinfunction "VM_2") (pintype "passive"))
    )
    (net (code "39") (name "Net-(U2-PROG)") (class "Default")
      (node (ref "R4") (pin "1") (pinfunction "1_1") (pintype "passive"))
      (node (ref "U2") (pin "2") (pinfunction "PROG_2") (pintype "passive"))
    )
    (net (code "40") (name "Net-(U2-~{CHRG})") (class "Default")
      (node (ref "R11") (pin "2") (pinfunction "2_2") (pintype "passive"))
      (node (ref "U2") (pin "7") (pinfunction "~{CHRG}_7") (pintype "passive"))
    )
    (net (code "41") (name "Net-(U2-~{STDBY})") (class "Default")
      (node (ref "R10") (pin "2") (pinfunction "2_2") (pintype "passive"))
      (node (ref "U2") (pin "6") (pinfunction "~{STDBY}_6") (pintype "passive"))
    )
    (net (code "42") (name "Net-(U5-FB)") (class "Default")
      (node (ref "R14") (pin "1") (pinfunction "1_1") (pintype "passive"))
      (node (ref "R24") (pin "2") (pinfunction "2_2") (pintype "passive"))
      (node (ref "U5") (pin "3") (pinfunction "FB_3") (pintype "passive"))
    )
    (net (code "43") (name "Net-(U5-VINA)") (class "Default")
      (node (ref "C20") (pin "1") (pinfunction "1_1") (pintype "passive"))
      (node (ref "U5") (pin "1") (pinfunction "VINA_1") (pintype "passive"))
      (node (ref "U5") (pin "13") (pinfunction "_PS/SYNC_13") (pintype "passive"))
    )
    (net (code "44") (name "OR_3.3V") (class "Default")
      (node (ref "D10") (pin "2") (pinfunction "K_2") (pintype "passive"))
      (node (ref "D11") (pin "2") (pinfunction "K_2") (pintype "passive"))
      (node (ref "Q3") (pin "2") (pinfunction "S_2") (pintype "passive"))
      (node (ref "Q4") (pin "2") (pinfunction "S_2") (pintype "passive"))
      (node (ref "R16") (pin "2") (pinfunction "2_2") (pintype "passive"))
      (node (ref "R31") (pin "2") (pinfunction "2_2") (pintype "passive"))
    )
    (net (code "45") (name "OUT{slash}BATT+") (class "Default")
      (node (ref "C11") (pin "1") (pinfunction "1_1") (pintype "passive"))
      (node (ref "C19") (pin "2") (pinfunction "2_2") (pintype "passive"))
      (node (ref "C3") (pin "2") (pinfunction "2_2") (pintype "passive"))
      (node (ref "J2") (pin "1") (pinfunction "1_1") (pintype "passive"))
      (node (ref "R1") (pin "2") (pinfunction "2_2") (pintype "passive"))
      (node (ref "R12") (pin "1") (pinfunction "1_1") (pintype "passive"))
      (node (ref "R21") (pin "1") (pinfunction "1_1") (pintype "passive"))
      (node (ref "U2") (pin "5") (pinfunction "BAT_5") (pintype "passive"))
      (node (ref "U5") (pin "10") (pinfunction "VIN_10") (pintype "passive"))
      (node (ref "U5") (pin "11") (pinfunction "VIN_11") (pintype "passive"))
      (node (ref "U8") (pin "3") (pinfunction "VCC_3") (pintype "passive"))
    )
    (net (code "46") (name "VUSB") (class "Default")
      (node (ref "C4") (pin "1") (pinfunction "1_1") (pintype "passive"))
      (node (ref "C5") (pin "1") (pinfunction "1_1") (pintype "passive"))
      (node (ref "D1") (pin "1") (pinfunction "1_1") (pintype "passive"))
      (node (ref "F1") (pin "1") (pinfunction "1_1") (pintype "passive"))
      (node (ref "J1") (pin "A4B9") (pinfunction "VBUS_A4B9") (pintype "passive"))
      (node (ref "J1") (pin "B4A9") (pinfunction "VBUS_B4A9") (pintype "passive"))
    )
    (net (code "47") (name "unconnected-(J1-SBU1-PadA8)") (class "Default")
      (node (ref "J1") (pin "A8") (pinfunction "SBU1_A8") (pintype "passive+no_connect"))
    )
    (net (code "48") (name "unconnected-(J1-SBU2-PadB8)") (class "Default")
      (node (ref "J1") (pin "B8") (pinfunction "SBU2_B8") (pintype "passive+no_connect"))
    )
    (net (code "49") (name "unconnected-(J2-Pad3)") (class "Default")
      (node (ref "J2") (pin "3") (pinfunction "3_3") (pintype "passive+no_connect"))
    )
    (net (code "50") (name "unconnected-(J2-Pad4)") (class "Default")
      (node (ref "J2") (pin "4") (pinfunction "4_4") (pintype "passive+no_connect"))
    )
    (net (code "51") (name "unconnected-(SW1-Pad1)") (class "Default")
      (node (ref "SW1") (pin "1") (pinfunction "1_1") (pintype "passive+no_connect"))
    )
    (net (code "52") (name "unconnected-(SW1-Pad3)") (class "Default")
      (node (ref "SW1") (pin "3") (pinfunction "3_3") (pintype "passive+no_connect"))
    )
    (net (code "53") (name "unconnected-(SW1-Pad5)") (class "Default")
      (node (ref "SW1") (pin "5") (pinfunction "5_5") (pintype "passive+no_connect"))
    )
    (net (code "54") (name "unconnected-(SW1-Pad6)") (class "Default")
      (node (ref "SW1") (pin "6") (pinfunction "6_6") (pintype "passive+no_connect"))
    )
    (net (code "55") (name "unconnected-(U1-NC-Pad4)") (class "Default")
      (node (ref "U1") (pin "4") (pinfunction "NC_4") (pintype "passive+no_connect"))
    )
    (net (code "56") (name "unconnected-(U3-D-Pad2)") (class "Default")
      (node (ref "U3") (pin "2") (pinfunction "D_2") (pintype "passive+no_connect"))
    )
    (net (code "57") (name "unconnected-(U3-D-Pad5)") (class "Default")
      (node (ref "U3") (pin "5") (pinfunction "D_5") (pintype "passive+no_connect"))
    )
    (net (code "58") (name "unconnected-(U5-PG-Pad14)") (class "Default")
      (node (ref "U5") (pin "14") (pinfunction "PG_14") (pintype "passive+no_connect"))
    )
  )
)
